# Drone.net
KiCad netlist of a schematic drawn in Altium Designer
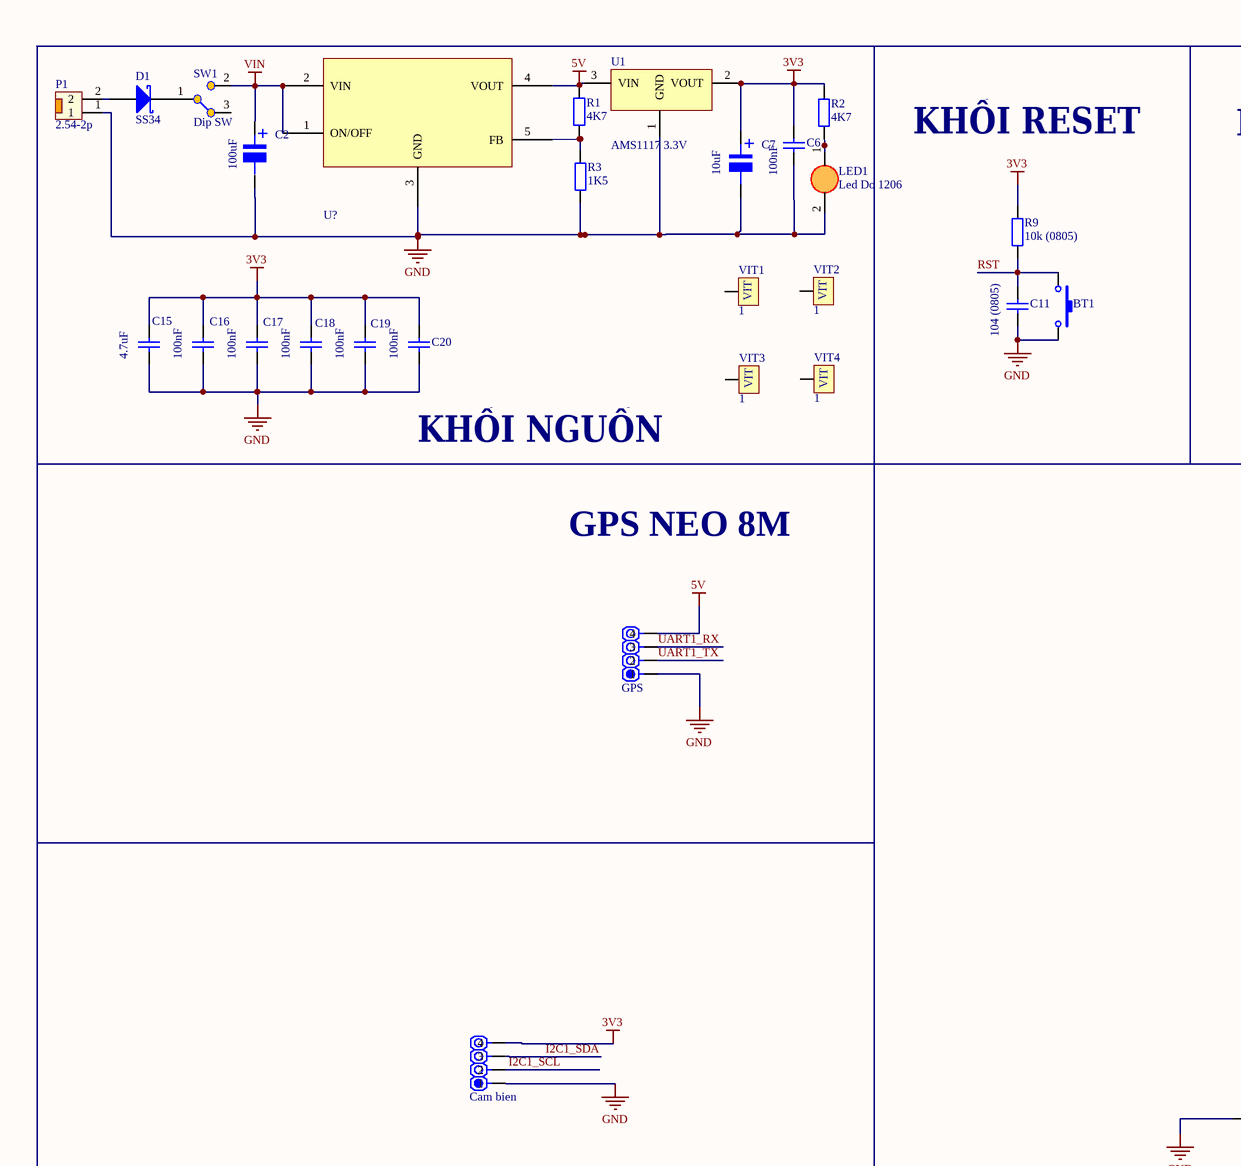
[diagram p0: Drone.SchDoc, top left]
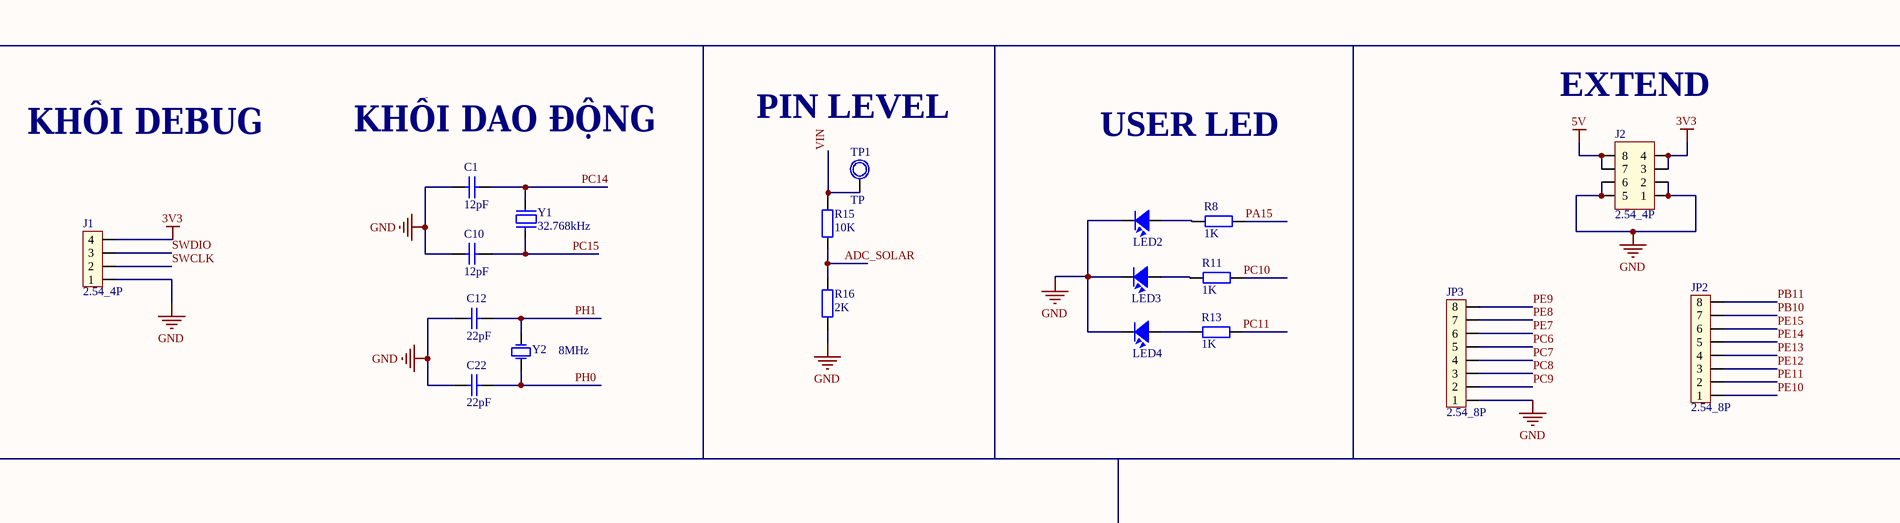
[diagram p1: Drone.SchDoc, top right]
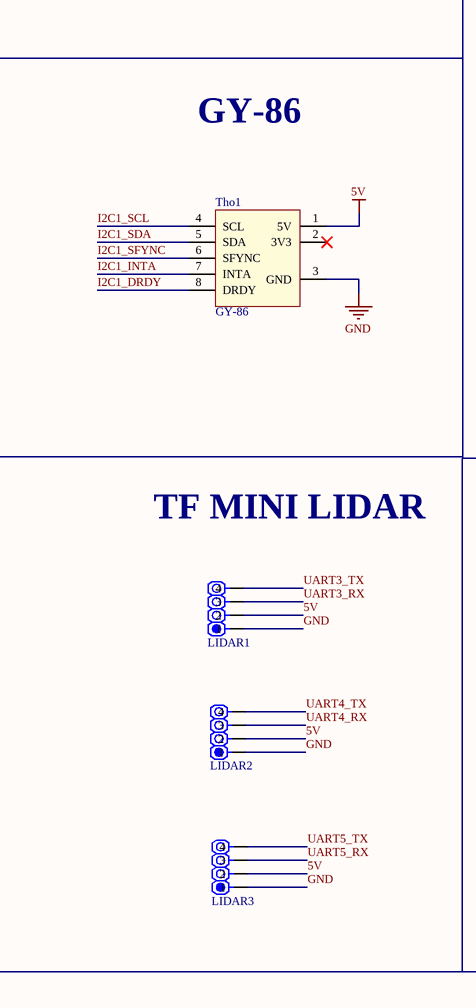
[diagram p2: Drone.SchDoc, bottom left]
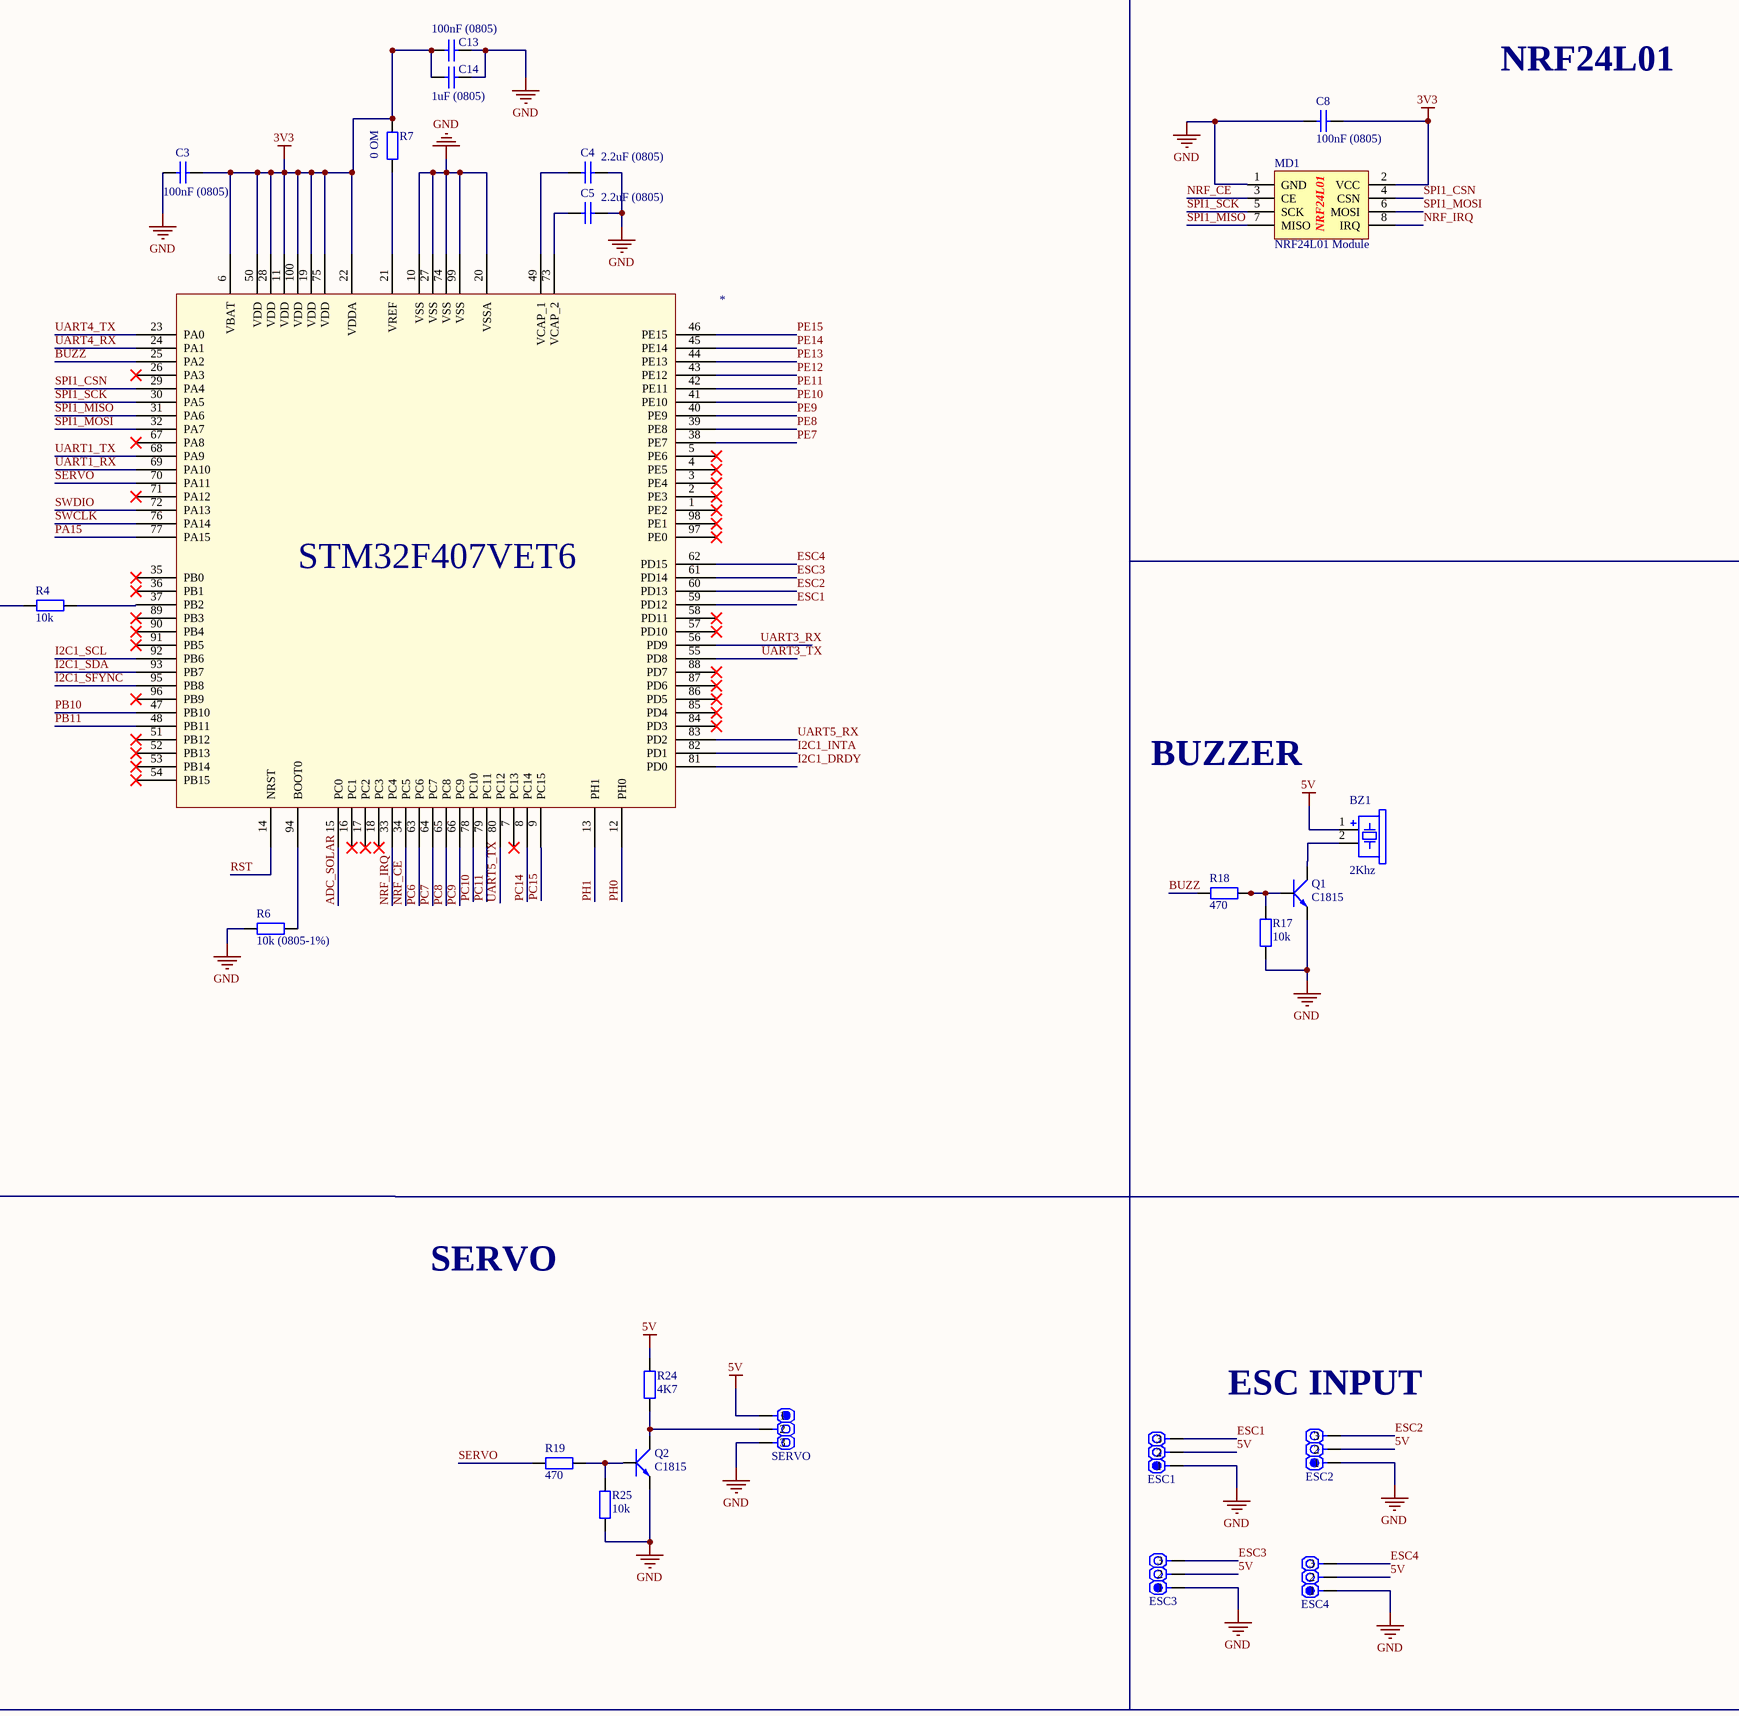
[diagram p3: Drone.SchDoc, bottom right]

(export (version "E")
  (design (tool "Eeschema 10.0.6"))
  (components
    (comp (ref "*")
      (value "STM32F407")
      (footprint "STM32F407Vet6")
      (libsource (lib "STM32f407") (part "STM32F407"))
    )
    (comp (ref "BT1")
      (value "Nút Nhấn 2 Chân 3x6x2.5MM SMD")
      (footprint "Nut Nhan 2 Chan SMD_N")
      (description "Dán")
      (libsource (lib "SCH Chuan") (part "Nut Nhan 2 Chan SMD"))
    )
    (comp (ref "BZ1")
      (value "2Khz")
      (footprint "coi xung")
      (description "Cắm")
      (libsource (lib "SCH Chuan") (part "Coi xung 2Khz"))
    )
    (comp (ref "C1")
      (value "12pF")
      (footprint "tu 0805")
      (description "Dán")
      (libsource (lib "SCH Chuan") (part "Tu 0805 10pF 50V 10%"))
    )
    (comp (ref "C2")
      (value "100uF")
      (footprint "tu nhom 10 (g)")
      (description "Dán")
      (libsource (lib "NhomLib") (part "Tu Nhom 100uF 35V"))
    )
    (comp (ref "C3")
      (value "100nF (0805)")
      (footprint "tu 0805")
      (description "Dán")
      (libsource (lib "SCH Chuan") (part "Tu 0805 220nF 50V 10%"))
    )
    (comp (ref "C4")
      (value "2.2uF (0805)")
      (footprint "tu 0805")
      (description "Dán")
      (libsource (lib "SCH Chuan") (part "Tu 0805 220nF 50V 10%"))
    )
    (comp (ref "C5")
      (value "2.2uF (0805)")
      (footprint "tu 0805")
      (description "Dán")
      (libsource (lib "SCH Chuan") (part "Tu 0805 220nF 50V 10%"))
    )
    (comp (ref "C6")
      (value "100nF")
      (footprint "tu 0805")
      (description "Dán")
      (libsource (lib "NhomLib") (part "Tu 0805 220nF 50V 10%"))
    )
    (comp (ref "C7")
      (value "10uF")
      (footprint "tu nhom 4 (b)")
      (description "Dán")
      (libsource (lib "NhomLib") (part "Tu Nhom 10uF 16V"))
    )
    (comp (ref "C8")
      (value "100nF (0805)")
      (footprint "tu 0805")
      (description "Dán")
      (libsource (lib "SCH Chuan") (part "Tu 0805 220nF 50V 10%"))
    )
    (comp (ref "C10")
      (value "12pF")
      (footprint "tu 0805")
      (description "Dán")
      (libsource (lib "SCH Chuan") (part "Tu 0805 10pF 50V 10%"))
    )
    (comp (ref "C11")
      (value "104 (0805)")
      (footprint "tu 0805")
      (description "Dán")
      (libsource (lib "SCH Chuan") (part "Tu 0805 104 50V 10%"))
    )
    (comp (ref "C12")
      (value "22pF")
      (footprint "tu 0805")
      (description "Dán")
      (libsource (lib "SCH Chuan") (part "Tu 0805 10pF 50V 10%"))
    )
    (comp (ref "C13")
      (value "100nF (0805)")
      (footprint "tu 0805")
      (description "Dán")
      (libsource (lib "SCH Chuan") (part "Tu 0805 220nF 50V 10%"))
    )
    (comp (ref "C14")
      (value "1uF (0805)")
      (footprint "tu 0805")
      (description "Dán")
      (libsource (lib "SCH Chuan") (part "Tu 0805 220nF 50V 10%"))
    )
    (comp (ref "C15")
      (value "4.7uF")
      (footprint "tu 0805")
      (description "Dán")
      (libsource (lib "SCH Chuan") (part "Tu 0805 104 50V 10%"))
    )
    (comp (ref "C16")
      (value "100nF")
      (footprint "tu 0805")
      (description "Dán")
      (libsource (lib "SCH Chuan") (part "Tu 0805 104 50V 10%"))
    )
    (comp (ref "C17")
      (value "100nF")
      (footprint "tu 0805")
      (description "Dán")
      (libsource (lib "SCH Chuan") (part "Tu 0805 104 50V 10%"))
    )
    (comp (ref "C18")
      (value "100nF")
      (footprint "tu 0805")
      (description "Dán")
      (libsource (lib "SCH Chuan") (part "Tu 0805 104 50V 10%"))
    )
    (comp (ref "C19")
      (value "100nF")
      (footprint "tu 0805")
      (description "Dán")
      (libsource (lib "SCH Chuan") (part "Tu 0805 104 50V 10%"))
    )
    (comp (ref "C20")
      (value "100nF")
      (footprint "tu 0805")
      (description "Dán")
      (libsource (lib "SCH Chuan") (part "Tu 0805 104 50V 10%"))
    )
    (comp (ref "C22")
      (value "22pF")
      (footprint "tu 0805")
      (description "Dán")
      (libsource (lib "SCH Chuan") (part "Tu 0805 10pF 50V 10%"))
    )
    (comp (ref "Cam bien")
      (value "IO")
      (footprint "CON.HDR1X4L")
      (description "Header 1x4")
      (fields (field (name "PUBLISHER") "NKIM"))
      (libsource (lib "VPMyLibrary") (part "CON.HDR1x4"))
    )
    (comp (ref "D1")
      (value "SS34")
      (footprint "DIODE_DO214AC_SMA")
      (description "DIODE SCHOTTKY 40V 3A SMA")
      (libsource (lib "NhomLib") (part "SS34"))
    )
    (comp (ref "ESC1")
      (value "IO")
      (footprint "CON.HDR1X3")
      (description "Header 1x3")
      (fields (field (name "PUBLISHER") "NKIM"))
      (libsource (lib "VPMyLibrary") (part "CON.HDR1x3"))
    )
    (comp (ref "ESC2")
      (value "IO")
      (footprint "CON.HDR1X3")
      (description "Header 1x3")
      (fields (field (name "PUBLISHER") "NKIM"))
      (libsource (lib "VPMyLibrary") (part "CON.HDR1x3"))
    )
    (comp (ref "ESC3")
      (value "IO")
      (footprint "CON.HDR1X3")
      (description "Header 1x3")
      (fields (field (name "PUBLISHER") "NKIM"))
      (libsource (lib "VPMyLibrary") (part "CON.HDR1x3"))
    )
    (comp (ref "ESC4")
      (value "IO")
      (footprint "CON.HDR1X3")
      (description "Header 1x3")
      (fields (field (name "PUBLISHER") "NKIM"))
      (libsource (lib "VPMyLibrary") (part "CON.HDR1x3"))
    )
    (comp (ref "GPS")
      (value "IO")
      (footprint "CON.HDR1X4L")
      (description "Header 1x4")
      (fields (field (name "PUBLISHER") "NKIM"))
      (libsource (lib "VPMyLibrary") (part "CON.HDR1x4"))
    )
    (comp (ref "J1")
      (value "2.54_4P")
      (footprint "jump don duc thang 2.54_4p")
      (description "Cắm")
      (libsource (lib "NhomLib") (part "Jump Don Duc Thang 2.54_4P"))
    )
    (comp (ref "J2")
      (value "2.54_4P")
      (footprint "JP4x2")
      (description "Cắm")
      (libsource (lib "NhomLib") (part "Jump Doi Duc 2.54_4Px2"))
    )
    (comp (ref "JP2")
      (value "2.54_8P")
      (footprint "Jump Don Duc Thang 2.54_8p")
      (description "Cắm")
      (libsource (lib "NhomLib") (part "Jump Don Duc 2.54_8P"))
    )
    (comp (ref "JP3")
      (value "2.54_8P")
      (footprint "Jump Don Duc Thang 2.54_8p")
      (description "Cắm")
      (libsource (lib "NhomLib") (part "Jump Don Duc 2.54_8P"))
    )
    (comp (ref "LED1")
      (value "Led Do 1206")
      (footprint "led 1206")
      (description "Dán")
      (libsource (lib "NhomLib") (part "Led 1206 Do"))
    )
    (comp (ref "LED2")
      (value "LED SMD")
      (footprint "SM-LED-0805-Yellow")
      (libsource (lib "syhaunguyen") (part "LED-SMD-0805"))
    )
    (comp (ref "LED3")
      (value "LED SMD")
      (footprint "SM-LED-0805-Green")
      (libsource (lib "syhaunguyen") (part "LED-SMD-0805"))
    )
    (comp (ref "LED4")
      (value "LED SMD")
      (footprint "SM-LED-0805-Blue")
      (libsource (lib "syhaunguyen") (part "LED-SMD-0805"))
    )
    (comp (ref "LIDAR1")
      (value "IO")
      (footprint "CON.HDR1X4L")
      (description "Header 1x4")
      (fields (field (name "PUBLISHER") "NKIM"))
      (libsource (lib "VPMyLibrary") (part "CON.HDR1x4"))
    )
    (comp (ref "LIDAR2")
      (value "IO")
      (footprint "CON.HDR1X4L")
      (description "Header 1x4")
      (fields (field (name "PUBLISHER") "NKIM"))
      (libsource (lib "VPMyLibrary") (part "CON.HDR1x4"))
    )
    (comp (ref "LIDAR3")
      (value "IO")
      (footprint "CON.HDR1X4L")
      (description "Header 1x4")
      (fields (field (name "PUBLISHER") "NKIM"))
      (libsource (lib "VPMyLibrary") (part "CON.HDR1x4"))
    )
    (comp (ref "MD1")
      (value "NRF24L01 Module")
      (footprint "NRF24L01")
      (libsource (lib "Altium_Lib_by_KhueNguyenCreator") (part "NRF24L01 Module"))
    )
    (comp (ref "MIC1")
      (value "U?")
      (footprint "Mic5V")
      (description "3A")
      (libsource (lib "node_mcu") (part "Mic5V"))
    )
    (comp (ref "P1")
      (value "2.54-2p")
      (footprint "Header Duc Thang 2P 2.54")
      (description "Cắm")
      (libsource (lib "NhomLib") (part "Header 2.54-2p Duc Thang"))
    )
    (comp (ref "Q1")
      (value "C1815")
      (footprint "SOT23B")
      (description "NPN 600mW, ECB")
      (libsource (lib "syhaunguyen") (part "C1815"))
    )
    (comp (ref "Q2")
      (value "C1815")
      (footprint "SOT23B")
      (description "NPN 600mW, ECB")
      (libsource (lib "syhaunguyen") (part "C1815"))
    )
    (comp (ref "R1")
      (value "4K7")
      (footprint "tro 0805")
      (description "Dán")
      (libsource (lib "SCH Chuan") (part "Tro 0805 5% 10k"))
    )
    (comp (ref "R2")
      (value "4K7")
      (footprint "tro 0805")
      (description "Dán")
      (libsource (lib "SCH Chuan") (part "Tro 0805 5% 10k"))
    )
    (comp (ref "R3")
      (value "1K5")
      (footprint "tro 0805")
      (description "Dán")
      (libsource (lib "SCH Chuan") (part "Tro 0805 5% 10k"))
    )
    (comp (ref "R4")
      (value "10k")
      (footprint "tro 0805")
      (description "Dán")
      (libsource (lib "SCH Chuan") (part "Tro 0805 1% 10k"))
    )
    (comp (ref "R6")
      (value "10k (0805-1%)")
      (footprint "tro 0805")
      (description "Dán")
      (libsource (lib "SCH Chuan") (part "Tro 0805 1% 10k"))
    )
    (comp (ref "R7")
      (value "0 OM")
      (footprint "tro 0805")
      (description "Dán")
      (libsource (lib "SCH Chuan") (part "Tro 0805 5% 10k"))
    )
    (comp (ref "R8")
      (value "1K")
      (footprint "tro 0805")
      (description "Dán")
      (libsource (lib "SCH Chuan") (part "Tro 0805 5% 470R"))
    )
    (comp (ref "R9")
      (value "10k (0805)")
      (footprint "tro 0805")
      (description "Dán")
      (libsource (lib "SCH Chuan") (part "Tro 0805 5% 10k"))
    )
    (comp (ref "R11")
      (value "1K")
      (footprint "tro 0805")
      (description "Dán")
      (libsource (lib "SCH Chuan") (part "Tro 0805 5% 470R"))
    )
    (comp (ref "R13")
      (value "1K")
      (footprint "tro 0805")
      (description "Dán")
      (libsource (lib "SCH Chuan") (part "Tro 0805 5% 470R"))
    )
    (comp (ref "R15")
      (value "10K")
      (footprint "tro 0805")
      (description "Dán")
      (libsource (lib "SCH Chuan") (part "Tro 0805 5% 10k"))
    )
    (comp (ref "R16")
      (value "2K")
      (footprint "tro 0805")
      (description "Dán")
      (libsource (lib "SCH Chuan") (part "Tro 0805 5% 10k"))
    )
    (comp (ref "R17")
      (value "10k")
      (footprint "tro 0805")
      (description "Dán")
      (libsource (lib "SCH Chuan") (part "Tro 0805 1% 10k"))
    )
    (comp (ref "R18")
      (value "470")
      (footprint "tro 0805")
      (description "Dán")
      (libsource (lib "SCH Chuan") (part "Tro 0805 1% 10k"))
    )
    (comp (ref "R19")
      (value "470")
      (footprint "tro 0805")
      (description "Dán")
      (libsource (lib "SCH Chuan") (part "Tro 0805 1% 10k"))
    )
    (comp (ref "R24")
      (value "4K7")
      (footprint "tro 0805")
      (description "Dán")
      (libsource (lib "SCH Chuan") (part "Tro 0805 1% 10k"))
    )
    (comp (ref "R25")
      (value "10k")
      (footprint "tro 0805")
      (description "Dán")
      (libsource (lib "SCH Chuan") (part "Tro 0805 1% 10k"))
    )
    (comp (ref "SERVO")
      (value "IO")
      (footprint "CON.HDR1X3")
      (description "Header 1x3")
      (fields (field (name "PUBLISHER") "NKIM"))
      (libsource (lib "VPMyLibrary") (part "CON.HDR1x3"))
    )
    (comp (ref "SW1")
      (value "Dip SW")
      (footprint "SW3P")
      (description "Dip Switch 3 pin")
      (libsource (lib "VPMyLibrary") (part "Switch3P"))
    )
    (comp (ref "Tho1") (value "GY-86") (footprint "GY-86") (libsource (lib "JOYSTICK") (part "GY-86")))
    (comp (ref "TP1")
      (value "TP")
      (footprint "TP1")
      (description "Test Point")
      (libsource (lib "syhaunguyen") (part "TP1"))
    )
    (comp (ref "U1")
      (value "AMS1117 3.3V")
      (footprint "SOT223")
      (description "Dán")
      (libsource (lib "NhomLib") (part "AMS1117 3.3V"))
    )
    (comp (ref "VIT1")
      (value "1")
      (footprint "VIT")
      (description "Oc Vit")
      (libsource (lib "NhomLib") (part "VIT"))
    )
    (comp (ref "VIT2")
      (value "1")
      (footprint "VIT")
      (description "Oc Vit")
      (libsource (lib "NhomLib") (part "VIT"))
    )
    (comp (ref "VIT3")
      (value "1")
      (footprint "VIT")
      (description "Oc Vit")
      (libsource (lib "NhomLib") (part "VIT"))
    )
    (comp (ref "VIT4")
      (value "1")
      (footprint "VIT")
      (description "Oc Vit")
      (libsource (lib "NhomLib") (part "VIT"))
    )
    (comp (ref "Y1")
      (value "32.768kHz")
      (footprint "Thach Anh 2 Chan 32,768 KHz")
      (description "Crystal For all Crystal 2pin.")
      (libsource (lib "Altium_Lib_by_KhueNguyenCreator") (part "Thach Anh 2 chan 32,768 Khz"))
    )
    (comp (ref "Y2")
      (value "8MHz")
      (footprint "thach anh 49s smd")
      (description "Dán")
      (libsource (lib "SCH Chuan") (part "Thach anh 8MHz 49S SMD"))
    )
  )
  (nets
    (net (code "1") (name "/ADC_SOLAR") (class "Default")
      (node (ref "*") (pin "15") (pinfunction "PC0_15") (pintype "passive"))
      (node (ref "R15") (pin "1") (pinfunction "1_1") (pintype "passive"))
      (node (ref "R16") (pin "2") (pinfunction "2_2") (pintype "passive"))
    )
    (net (code "2") (name "/BUZZ") (class "Default")
      (node (ref "*") (pin "25") (pinfunction "PA2_25") (pintype "passive"))
      (node (ref "R18") (pin "2") (pinfunction "2_2") (pintype "passive"))
    )
    (net (code "3") (name "/ESC1") (class "Default")
      (node (ref "*") (pin "59") (pinfunction "PD12_59") (pintype "passive"))
      (node (ref "ESC1") (pin "3") (pinfunction "3_3") (pintype "passive"))
    )
    (net (code "4") (name "/ESC2") (class "Default")
      (node (ref "*") (pin "60") (pinfunction "PD13_60") (pintype "passive"))
      (node (ref "ESC2") (pin "3") (pinfunction "3_3") (pintype "passive"))
    )
    (net (code "5") (name "/ESC3") (class "Default")
      (node (ref "*") (pin "61") (pinfunction "PD14_61") (pintype "passive"))
      (node (ref "ESC3") (pin "3") (pinfunction "3_3") (pintype "passive"))
    )
    (net (code "6") (name "/ESC4") (class "Default")
      (node (ref "*") (pin "62") (pinfunction "PD15_62") (pintype "passive"))
      (node (ref "ESC4") (pin "3") (pinfunction "3_3") (pintype "passive"))
    )
    (net (code "7") (name "/I2C1_DRDY") (class "Default")
      (node (ref "*") (pin "81") (pinfunction "PD0_81") (pintype "passive"))
      (node (ref "Tho1") (pin "8") (pinfunction "DRDY_8") (pintype "passive"))
    )
    (net (code "8") (name "/I2C1_INTA") (class "Default")
      (node (ref "*") (pin "82") (pinfunction "PD1_82") (pintype "passive"))
      (node (ref "Tho1") (pin "7") (pinfunction "INTA_7") (pintype "passive"))
    )
    (net (code "9") (name "/I2C1_SCL") (class "Default")
      (node (ref "*") (pin "92") (pinfunction "PB6_92") (pintype "passive"))
      (node (ref "Cam bien") (pin "2") (pinfunction "2_2") (pintype "passive"))
      (node (ref "Tho1") (pin "4") (pinfunction "SCL_4") (pintype "passive"))
    )
    (net (code "10") (name "/I2C1_SDA") (class "Default")
      (node (ref "*") (pin "93") (pinfunction "PB7_93") (pintype "passive"))
      (node (ref "Cam bien") (pin "3") (pinfunction "3_3") (pintype "passive"))
      (node (ref "Tho1") (pin "5") (pinfunction "SDA_5") (pintype "passive"))
    )
    (net (code "11") (name "/I2C1_SFYNC") (class "Default")
      (node (ref "*") (pin "95") (pinfunction "PB8_95") (pintype "passive"))
      (node (ref "Tho1") (pin "6") (pinfunction "SFYNC_6") (pintype "passive"))
    )
    (net (code "12") (name "/NRF_CE") (class "Default")
      (node (ref "*") (pin "34") (pinfunction "PC5_34") (pintype "passive"))
      (node (ref "MD1") (pin "3") (pinfunction "CE_3") (pintype "passive"))
    )
    (net (code "13") (name "/NRF_IRQ") (class "Default")
      (node (ref "*") (pin "33") (pinfunction "PC4_33") (pintype "passive"))
      (node (ref "MD1") (pin "8") (pinfunction "IRQ_8") (pintype "passive"))
    )
    (net (code "14") (name "/PA15") (class "Default")
      (node (ref "*") (pin "77") (pinfunction "PA15_77") (pintype "passive"))
      (node (ref "R8") (pin "2") (pinfunction "2_2") (pintype "passive"))
    )
    (net (code "15") (name "/PB10") (class "Default")
      (node (ref "*") (pin "47") (pinfunction "PB10_47") (pintype "passive"))
      (node (ref "JP2") (pin "7") (pinfunction "7_7") (pintype "passive"))
    )
    (net (code "16") (name "/PB11") (class "Default")
      (node (ref "*") (pin "48") (pinfunction "PB11_48") (pintype "passive"))
      (node (ref "JP2") (pin "8") (pinfunction "8_8") (pintype "passive"))
    )
    (net (code "17") (name "/PC6") (class "Default")
      (node (ref "*") (pin "63") (pinfunction "PC6_63") (pintype "passive"))
      (node (ref "JP3") (pin "5") (pinfunction "5_5") (pintype "passive"))
    )
    (net (code "18") (name "/PC7") (class "Default")
      (node (ref "*") (pin "64") (pinfunction "PC7_64") (pintype "passive"))
      (node (ref "JP3") (pin "4") (pinfunction "4_4") (pintype "passive"))
    )
    (net (code "19") (name "/PC8") (class "Default")
      (node (ref "*") (pin "65") (pinfunction "PC8_65") (pintype "passive"))
      (node (ref "JP3") (pin "3") (pinfunction "3_3") (pintype "passive"))
    )
    (net (code "20") (name "/PC9") (class "Default")
      (node (ref "*") (pin "66") (pinfunction "PC9_66") (pintype "passive"))
      (node (ref "JP3") (pin "2") (pinfunction "2_2") (pintype "passive"))
    )
    (net (code "21") (name "/PC10") (class "Default")
      (node (ref "*") (pin "78") (pinfunction "PC10_78") (pintype "passive"))
      (node (ref "R11") (pin "2") (pinfunction "2_2") (pintype "passive"))
    )
    (net (code "22") (name "/PC11") (class "Default")
      (node (ref "*") (pin "79") (pinfunction "PC11_79") (pintype "passive"))
      (node (ref "R13") (pin "2") (pinfunction "2_2") (pintype "passive"))
    )
    (net (code "23") (name "/PC14") (class "Default")
      (node (ref "*") (pin "8") (pinfunction "PC14_8") (pintype "passive"))
      (node (ref "C1") (pin "1") (pinfunction "1_1") (pintype "passive"))
      (node (ref "Y1") (pin "2") (pinfunction "2_2") (pintype "passive"))
    )
    (net (code "24") (name "/PC15") (class "Default")
      (node (ref "*") (pin "9") (pinfunction "PC15_9") (pintype "passive"))
      (node (ref "C10") (pin "1") (pinfunction "1_1") (pintype "passive"))
      (node (ref "Y1") (pin "1") (pinfunction "1_1") (pintype "passive"))
    )
    (net (code "25") (name "/PE7") (class "Default")
      (node (ref "*") (pin "38") (pinfunction "PE7_38") (pintype "passive"))
      (node (ref "JP3") (pin "6") (pinfunction "6_6") (pintype "passive"))
    )
    (net (code "26") (name "/PE8") (class "Default")
      (node (ref "*") (pin "39") (pinfunction "PE8_39") (pintype "passive"))
      (node (ref "JP3") (pin "7") (pinfunction "7_7") (pintype "passive"))
    )
    (net (code "27") (name "/PE9") (class "Default")
      (node (ref "*") (pin "40") (pinfunction "PE9_40") (pintype "passive"))
      (node (ref "JP3") (pin "8") (pinfunction "8_8") (pintype "passive"))
    )
    (net (code "28") (name "/PE10") (class "Default")
      (node (ref "*") (pin "41") (pinfunction "PE10_41") (pintype "passive"))
      (node (ref "JP2") (pin "1") (pinfunction "1_1") (pintype "passive"))
    )
    (net (code "29") (name "/PE11") (class "Default")
      (node (ref "*") (pin "42") (pinfunction "PE11_42") (pintype "passive"))
      (node (ref "JP2") (pin "2") (pinfunction "2_2") (pintype "passive"))
    )
    (net (code "30") (name "/PE12") (class "Default")
      (node (ref "*") (pin "43") (pinfunction "PE12_43") (pintype "passive"))
      (node (ref "JP2") (pin "3") (pinfunction "3_3") (pintype "passive"))
    )
    (net (code "31") (name "/PE13") (class "Default")
      (node (ref "*") (pin "44") (pinfunction "PE13_44") (pintype "passive"))
      (node (ref "JP2") (pin "4") (pinfunction "4_4") (pintype "passive"))
    )
    (net (code "32") (name "/PE14") (class "Default")
      (node (ref "*") (pin "45") (pinfunction "PE14_45") (pintype "passive"))
      (node (ref "JP2") (pin "5") (pinfunction "5_5") (pintype "passive"))
    )
    (net (code "33") (name "/PE15") (class "Default")
      (node (ref "*") (pin "46") (pinfunction "PE15_46") (pintype "passive"))
      (node (ref "JP2") (pin "6") (pinfunction "6_6") (pintype "passive"))
    )
    (net (code "34") (name "/PH0") (class "Default")
      (node (ref "*") (pin "12") (pinfunction "PH0_12") (pintype "passive"))
      (node (ref "C22") (pin "1") (pinfunction "1_1") (pintype "passive"))
      (node (ref "Y2") (pin "2") (pinfunction "OSC2_2") (pintype "passive"))
    )
    (net (code "35") (name "/PH1") (class "Default")
      (node (ref "*") (pin "13") (pinfunction "PH1_13") (pintype "passive"))
      (node (ref "C12") (pin "1") (pinfunction "1_1") (pintype "passive"))
      (node (ref "Y2") (pin "1") (pinfunction "OSC1_1") (pintype "passive"))
    )
    (net (code "36") (name "/RST") (class "Default")
      (node (ref "*") (pin "14") (pinfunction "NRST_14") (pintype "passive"))
      (node (ref "BT1") (pin "1") (pinfunction "1_1") (pintype "passive"))
      (node (ref "C11") (pin "1") (pinfunction "1_1") (pintype "passive"))
      (node (ref "R9") (pin "1") (pinfunction "1_1") (pintype "passive"))
    )
    (net (code "37") (name "/SERVO") (class "Default")
      (node (ref "*") (pin "70") (pinfunction "PA11_70") (pintype "passive"))
      (node (ref "R19") (pin "2") (pinfunction "2_2") (pintype "passive"))
    )
    (net (code "38") (name "/SPI1_CSN") (class "Default")
      (node (ref "*") (pin "29") (pinfunction "PA4_29") (pintype "passive"))
      (node (ref "MD1") (pin "4") (pinfunction "CSN_4") (pintype "passive"))
    )
    (net (code "39") (name "/SPI1_MISO") (class "Default")
      (node (ref "*") (pin "31") (pinfunction "PA6_31") (pintype "passive"))
      (node (ref "MD1") (pin "7") (pinfunction "MISO_7") (pintype "passive"))
    )
    (net (code "40") (name "/SPI1_MOSI") (class "Default")
      (node (ref "*") (pin "32") (pinfunction "PA7_32") (pintype "passive"))
      (node (ref "MD1") (pin "6") (pinfunction "MOSI_6") (pintype "passive"))
    )
    (net (code "41") (name "/SPI1_SCK") (class "Default")
      (node (ref "*") (pin "30") (pinfunction "PA5_30") (pintype "passive"))
      (node (ref "MD1") (pin "5") (pinfunction "SCK_5") (pintype "passive"))
    )
    (net (code "42") (name "/SWCLK") (class "Default")
      (node (ref "*") (pin "76") (pinfunction "PA14_76") (pintype "passive"))
      (node (ref "J1") (pin "2") (pinfunction "2_2") (pintype "passive"))
    )
    (net (code "43") (name "/SWDIO") (class "Default")
      (node (ref "*") (pin "72") (pinfunction "PA13_72") (pintype "passive"))
      (node (ref "J1") (pin "3") (pinfunction "3_3") (pintype "passive"))
    )
    (net (code "44") (name "/UART1_RX") (class "Default")
      (node (ref "*") (pin "69") (pinfunction "PA10_69") (pintype "passive"))
      (node (ref "GPS") (pin "3") (pinfunction "3_3") (pintype "passive"))
    )
    (net (code "45") (name "/UART1_TX") (class "Default")
      (node (ref "*") (pin "68") (pinfunction "PA9_68") (pintype "passive"))
      (node (ref "GPS") (pin "2") (pinfunction "2_2") (pintype "passive"))
    )
    (net (code "46") (name "/UART3_RX") (class "Default")
      (node (ref "*") (pin "56") (pinfunction "PD9_56") (pintype "passive"))
      (node (ref "LIDAR1") (pin "3") (pinfunction "3_3") (pintype "passive"))
    )
    (net (code "47") (name "/UART3_TX") (class "Default")
      (node (ref "*") (pin "55") (pinfunction "PD8_55") (pintype "passive"))
      (node (ref "LIDAR1") (pin "4") (pinfunction "4_4") (pintype "passive"))
    )
    (net (code "48") (name "/UART4_RX") (class "Default")
      (node (ref "*") (pin "24") (pinfunction "PA1_24") (pintype "passive"))
      (node (ref "LIDAR2") (pin "3") (pinfunction "3_3") (pintype "passive"))
    )
    (net (code "49") (name "/UART4_TX") (class "Default")
      (node (ref "*") (pin "23") (pinfunction "PA0_23") (pintype "passive"))
      (node (ref "LIDAR2") (pin "4") (pinfunction "4_4") (pintype "passive"))
    )
    (net (code "50") (name "/UART5_RX") (class "Default")
      (node (ref "*") (pin "83") (pinfunction "PD2_83") (pintype "passive"))
      (node (ref "LIDAR3") (pin "3") (pinfunction "3_3") (pintype "passive"))
    )
    (net (code "51") (name "/UART5_TX") (class "Default")
      (node (ref "*") (pin "80") (pinfunction "PC12_80") (pintype "passive"))
      (node (ref "LIDAR3") (pin "4") (pinfunction "4_4") (pintype "passive"))
    )
    (net (code "52") (name "3V3") (class "Default")
      (node (ref "*") (pin "100") (pinfunction "VDD_100") (pintype "passive"))
      (node (ref "*") (pin "11") (pinfunction "VDD_11") (pintype "passive"))
      (node (ref "*") (pin "19") (pinfunction "VDD_19") (pintype "passive"))
      (node (ref "*") (pin "22") (pinfunction "VDDA_22") (pintype "passive"))
      (node (ref "*") (pin "28") (pinfunction "VDD_28") (pintype "passive"))
      (node (ref "*") (pin "50") (pinfunction "VDD_50") (pintype "passive"))
      (node (ref "*") (pin "6") (pinfunction "VBAT_6") (pintype "passive"))
      (node (ref "*") (pin "75") (pinfunction "VDD_75") (pintype "passive"))
      (node (ref "C13") (pin "2") (pinfunction "2_2") (pintype "passive"))
      (node (ref "C14") (pin "2") (pinfunction "2_2") (pintype "passive"))
      (node (ref "C15") (pin "1") (pinfunction "1_1") (pintype "passive"))
      (node (ref "C16") (pin "1") (pinfunction "1_1") (pintype "passive"))
      (node (ref "C17") (pin "1") (pinfunction "1_1") (pintype "passive"))
      (node (ref "C18") (pin "1") (pinfunction "1_1") (pintype "passive"))
      (node (ref "C19") (pin "1") (pinfunction "1_1") (pintype "passive"))
      (node (ref "C20") (pin "1") (pinfunction "1_1") (pintype "passive"))
      (node (ref "C3") (pin "1") (pinfunction "1_1") (pintype "passive"))
      (node (ref "C6") (pin "1") (pinfunction "1_1") (pintype "passive"))
      (node (ref "C7") (pin "1") (pinfunction "1_1") (pintype "passive"))
      (node (ref "C8") (pin "2") (pinfunction "2_2") (pintype "passive"))
      (node (ref "Cam bien") (pin "4") (pinfunction "4_4") (pintype "passive"))
      (node (ref "J1") (pin "4") (pinfunction "4_4") (pintype "passive"))
      (node (ref "J2") (pin "3") (pinfunction "3_3") (pintype "passive"))
      (node (ref "J2") (pin "4") (pinfunction "4_4") (pintype "passive"))
      (node (ref "MD1") (pin "2") (pinfunction "VCC_2") (pintype "passive"))
      (node (ref "R2") (pin "1") (pinfunction "1_1") (pintype "passive"))
      (node (ref "R7") (pin "2") (pinfunction "2_2") (pintype "passive"))
      (node (ref "R9") (pin "2") (pinfunction "2_2") (pintype "passive"))
      (node (ref "U1") (pin "2") (pinfunction "VOUT_2") (pintype "passive"))
    )
    (net (code "53") (name "5V") (class "Default")
      (node (ref "BZ1") (pin "1") (pinfunction "1_1") (pintype "passive"))
      (node (ref "ESC1") (pin "2") (pinfunction "2_2") (pintype "passive"))
      (node (ref "ESC2") (pin "2") (pinfunction "2_2") (pintype "passive"))
      (node (ref "ESC3") (pin "2") (pinfunction "2_2") (pintype "passive"))
      (node (ref "ESC4") (pin "2") (pinfunction "2_2") (pintype "passive"))
      (node (ref "GPS") (pin "4") (pinfunction "4_4") (pintype "passive"))
      (node (ref "J2") (pin "7") (pinfunction "7_7") (pintype "passive"))
      (node (ref "J2") (pin "8") (pinfunction "8_8") (pintype "passive"))
      (node (ref "LIDAR1") (pin "2") (pinfunction "2_2") (pintype "passive"))
      (node (ref "LIDAR2") (pin "2") (pinfunction "2_2") (pintype "passive"))
      (node (ref "LIDAR3") (pin "2") (pinfunction "2_2") (pintype "passive"))
      (node (ref "MIC1") (pin "4") (pinfunction "VOUT_4") (pintype "passive"))
      (node (ref "R1") (pin "2") (pinfunction "2_2") (pintype "passive"))
      (node (ref "R24") (pin "2") (pinfunction "2_2") (pintype "passive"))
      (node (ref "SERVO") (pin "1") (pinfunction "1_1") (pintype "passive"))
      (node (ref "Tho1") (pin "1") (pinfunction "5V_1") (pintype "passive"))
      (node (ref "U1") (pin "3") (pinfunction "VIN_3") (pintype "passive"))
    )
    (net (code "54") (name "GND") (class "Default")
      (node (ref "*") (pin "10") (pinfunction "VSS_10") (pintype "passive"))
      (node (ref "*") (pin "20") (pinfunction "VSSA_20") (pintype "passive"))
      (node (ref "*") (pin "27") (pinfunction "VSS_27") (pintype "passive"))
      (node (ref "*") (pin "74") (pinfunction "VSS_74") (pintype "passive"))
      (node (ref "*") (pin "99") (pinfunction "VSS_99") (pintype "passive"))
      (node (ref "BT1") (pin "2") (pinfunction "2_2") (pintype "passive"))
      (node (ref "C1") (pin "2") (pinfunction "2_2") (pintype "passive"))
      (node (ref "C10") (pin "2") (pinfunction "2_2") (pintype "passive"))
      (node (ref "C11") (pin "2") (pinfunction "2_2") (pintype "passive"))
      (node (ref "C12") (pin "2") (pinfunction "2_2") (pintype "passive"))
      (node (ref "C13") (pin "1") (pinfunction "1_1") (pintype "passive"))
      (node (ref "C14") (pin "1") (pinfunction "1_1") (pintype "passive"))
      (node (ref "C15") (pin "2") (pinfunction "2_2") (pintype "passive"))
      (node (ref "C16") (pin "2") (pinfunction "2_2") (pintype "passive"))
      (node (ref "C17") (pin "2") (pinfunction "2_2") (pintype "passive"))
      (node (ref "C18") (pin "2") (pinfunction "2_2") (pintype "passive"))
      (node (ref "C19") (pin "2") (pinfunction "2_2") (pintype "passive"))
      (node (ref "C2") (pin "2") (pinfunction "2_2") (pintype "passive"))
      (node (ref "C20") (pin "2") (pinfunction "2_2") (pintype "passive"))
      (node (ref "C22") (pin "2") (pinfunction "2_2") (pintype "passive"))
      (node (ref "C3") (pin "2") (pinfunction "2_2") (pintype "passive"))
      (node (ref "C4") (pin "1") (pinfunction "1_1") (pintype "passive"))
      (node (ref "C5") (pin "1") (pinfunction "1_1") (pintype "passive"))
      (node (ref "C6") (pin "2") (pinfunction "2_2") (pintype "passive"))
      (node (ref "C7") (pin "2") (pinfunction "2_2") (pintype "passive"))
      (node (ref "C8") (pin "1") (pinfunction "1_1") (pintype "passive"))
      (node (ref "Cam bien") (pin "1") (pinfunction "1_1") (pintype "passive"))
      (node (ref "ESC1") (pin "1") (pinfunction "1_1") (pintype "passive"))
      (node (ref "ESC2") (pin "1") (pinfunction "1_1") (pintype "passive"))
      (node (ref "ESC3") (pin "1") (pinfunction "1_1") (pintype "passive"))
      (node (ref "ESC4") (pin "1") (pinfunction "1_1") (pintype "passive"))
      (node (ref "GPS") (pin "1") (pinfunction "1_1") (pintype "passive"))
      (node (ref "J1") (pin "1") (pinfunction "1_1") (pintype "passive"))
      (node (ref "J2") (pin "1") (pinfunction "1_1") (pintype "passive"))
      (node (ref "J2") (pin "2") (pinfunction "2_2") (pintype "passive"))
      (node (ref "J2") (pin "5") (pinfunction "5_5") (pintype "passive"))
      (node (ref "J2") (pin "6") (pinfunction "6_6") (pintype "passive"))
      (node (ref "JP3") (pin "1") (pinfunction "1_1") (pintype "passive"))
      (node (ref "LED1") (pin "2") (pinfunction "K_2") (pintype "passive"))
      (node (ref "LED2") (pin "2") (pinfunction "2_2") (pintype "passive"))
      (node (ref "LED3") (pin "2") (pinfunction "2_2") (pintype "passive"))
      (node (ref "LED4") (pin "2") (pinfunction "2_2") (pintype "passive"))
      (node (ref "LIDAR1") (pin "1") (pinfunction "1_1") (pintype "passive"))
      (node (ref "LIDAR2") (pin "1") (pinfunction "1_1") (pintype "passive"))
      (node (ref "LIDAR3") (pin "1") (pinfunction "1_1") (pintype "passive"))
      (node (ref "MD1") (pin "1") (pinfunction "GND_1") (pintype "passive"))
      (node (ref "MIC1") (pin "3") (pinfunction "GND_3") (pintype "passive"))
      (node (ref "P1") (pin "1") (pinfunction "1_1") (pintype "passive"))
      (node (ref "Q1") (pin "1") (pinfunction "E_1") (pintype "passive"))
      (node (ref "Q2") (pin "1") (pinfunction "E_1") (pintype "passive"))
      (node (ref "R16") (pin "1") (pinfunction "1_1") (pintype "passive"))
      (node (ref "R17") (pin "1") (pinfunction "1_1") (pintype "passive"))
      (node (ref "R25") (pin "1") (pinfunction "1_1") (pintype "passive"))
      (node (ref "R3") (pin "1") (pinfunction "1_1") (pintype "passive"))
      (node (ref "R4") (pin "1") (pinfunction "1_1") (pintype "passive"))
      (node (ref "R6") (pin "1") (pinfunction "1_1") (pintype "passive"))
      (node (ref "SERVO") (pin "3") (pinfunction "3_3") (pintype "passive"))
      (node (ref "Tho1") (pin "3") (pinfunction "GND_3") (pintype "passive"))
      (node (ref "U1") (pin "1") (pinfunction "GND_1") (pintype "passive"))
    )
    (net (code "55") (name "Net-(*-BOOT0)") (class "Default")
      (node (ref "*") (pin "94") (pinfunction "BOOT0_94") (pintype "passive"))
      (node (ref "R6") (pin "2") (pinfunction "2_2") (pintype "passive"))
    )
    (net (code "56") (name "Net-(*-PB2)") (class "Default")
      (node (ref "*") (pin "37") (pinfunction "PB2_37") (pintype "passive"))
      (node (ref "R4") (pin "2") (pinfunction "2_2") (pintype "passive"))
    )
    (net (code "57") (name "Net-(*-VCAP_1)") (class "Default")
      (node (ref "*") (pin "49") (pinfunction "VCAP_1_49") (pintype "passive"))
      (node (ref "C4") (pin "2") (pinfunction "2_2") (pintype "passive"))
    )
    (net (code "58") (name "Net-(*-VCAP_2)") (class "Default")
      (node (ref "*") (pin "73") (pinfunction "VCAP_2_73") (pintype "passive"))
      (node (ref "C5") (pin "2") (pinfunction "2_2") (pintype "passive"))
    )
    (net (code "59") (name "Net-(*-VREF)") (class "Default")
      (node (ref "*") (pin "21") (pinfunction "VREF_21") (pintype "passive"))
      (node (ref "R7") (pin "1") (pinfunction "1_1") (pintype "passive"))
    )
    (net (code "60") (name "Net-(D1-A)") (class "Default")
      (node (ref "D1") (pin "1") (pinfunction "A_1") (pintype "passive"))
      (node (ref "P1") (pin "2") (pinfunction "2_2") (pintype "passive"))
    )
    (net (code "61") (name "Net-(D1-K)") (class "Default")
      (node (ref "D1") (pin "2") (pinfunction "K_2") (pintype "passive"))
      (node (ref "SW1") (pin "1") (pinfunction "COM_1") (pintype "passive"))
    )
    (net (code "62") (name "Net-(LED1-A)") (class "Default")
      (node (ref "LED1") (pin "1") (pinfunction "A_1") (pintype "passive"))
      (node (ref "R2") (pin "2") (pinfunction "2_2") (pintype "passive"))
    )
    (net (code "63") (name "Net-(LED2-Pad1)") (class "Default")
      (node (ref "LED2") (pin "1") (pinfunction "1_1") (pintype "passive"))
      (node (ref "R8") (pin "1") (pinfunction "1_1") (pintype "passive"))
    )
    (net (code "64") (name "Net-(LED3-Pad1)") (class "Default")
      (node (ref "LED3") (pin "1") (pinfunction "1_1") (pintype "passive"))
      (node (ref "R11") (pin "1") (pinfunction "1_1") (pintype "passive"))
    )
    (net (code "65") (name "Net-(LED4-Pad1)") (class "Default")
      (node (ref "LED4") (pin "1") (pinfunction "1_1") (pintype "passive"))
      (node (ref "R13") (pin "1") (pinfunction "1_1") (pintype "passive"))
    )
    (net (code "66") (name "Net-(MIC1-FB)") (class "Default")
      (node (ref "MIC1") (pin "5") (pinfunction "FB_5") (pintype "passive"))
      (node (ref "R1") (pin "1") (pinfunction "1_1") (pintype "passive"))
      (node (ref "R3") (pin "2") (pinfunction "2_2") (pintype "passive"))
    )
    (net (code "67") (name "Net-(Q1-B)") (class "Default")
      (node (ref "Q1") (pin "3") (pinfunction "B_3") (pintype "passive"))
      (node (ref "R17") (pin "2") (pinfunction "2_2") (pintype "passive"))
      (node (ref "R18") (pin "1") (pinfunction "1_1") (pintype "passive"))
    )
    (net (code "68") (name "Net-(Q1-C)") (class "Default")
      (node (ref "BZ1") (pin "2") (pinfunction "2_2") (pintype "passive"))
      (node (ref "Q1") (pin "2") (pinfunction "C_2") (pintype "passive"))
    )
    (net (code "69") (name "Net-(Q2-B)") (class "Default")
      (node (ref "Q2") (pin "3") (pinfunction "B_3") (pintype "passive"))
      (node (ref "R19") (pin "1") (pinfunction "1_1") (pintype "passive"))
      (node (ref "R25") (pin "2") (pinfunction "2_2") (pintype "passive"))
    )
    (net (code "70") (name "Net-(Q2-C)") (class "Default")
      (node (ref "Q2") (pin "2") (pinfunction "C_2") (pintype "passive"))
      (node (ref "R24") (pin "1") (pinfunction "1_1") (pintype "passive"))
      (node (ref "SERVO") (pin "2") (pinfunction "2_2") (pintype "passive"))
    )
    (net (code "71") (name "VIN") (class "Default")
      (node (ref "C2") (pin "1") (pinfunction "1_1") (pintype "passive"))
      (node (ref "MIC1") (pin "1") (pinfunction "ON/OFF_1") (pintype "passive"))
      (node (ref "MIC1") (pin "2") (pinfunction "VIN_2") (pintype "passive"))
      (node (ref "R15") (pin "2") (pinfunction "2_2") (pintype "passive"))
      (node (ref "SW1") (pin "2") (pinfunction "NC_2") (pintype "passive"))
      (node (ref "TP1") (pin "1") (pinfunction "1_1") (pintype "passive"))
    )
    (net (code "72") (name "unconnected-(*-PA3-Pad26)") (class "Default")
      (node (ref "*") (pin "26") (pinfunction "PA3_26") (pintype "passive+no_connect"))
    )
    (net (code "73") (name "unconnected-(*-PA8-Pad67)") (class "Default")
      (node (ref "*") (pin "67") (pinfunction "PA8_67") (pintype "passive+no_connect"))
    )
    (net (code "74") (name "unconnected-(*-PA12-Pad71)") (class "Default")
      (node (ref "*") (pin "71") (pinfunction "PA12_71") (pintype "passive+no_connect"))
    )
    (net (code "75") (name "unconnected-(*-PB0-Pad35)") (class "Default")
      (node (ref "*") (pin "35") (pinfunction "PB0_35") (pintype "passive+no_connect"))
    )
    (net (code "76") (name "unconnected-(*-PB1-Pad36)") (class "Default")
      (node (ref "*") (pin "36") (pinfunction "PB1_36") (pintype "passive+no_connect"))
    )
    (net (code "77") (name "unconnected-(*-PB3-Pad89)") (class "Default")
      (node (ref "*") (pin "89") (pinfunction "PB3_89") (pintype "passive+no_connect"))
    )
    (net (code "78") (name "unconnected-(*-PB4-Pad90)") (class "Default")
      (node (ref "*") (pin "90") (pinfunction "PB4_90") (pintype "passive+no_connect"))
    )
    (net (code "79") (name "unconnected-(*-PB5-Pad91)") (class "Default")
      (node (ref "*") (pin "91") (pinfunction "PB5_91") (pintype "passive+no_connect"))
    )
    (net (code "80") (name "unconnected-(*-PB9-Pad96)") (class "Default")
      (node (ref "*") (pin "96") (pinfunction "PB9_96") (pintype "passive+no_connect"))
    )
    (net (code "81") (name "unconnected-(*-PB12-Pad51)") (class "Default")
      (node (ref "*") (pin "51") (pinfunction "PB12_51") (pintype "passive+no_connect"))
    )
    (net (code "82") (name "unconnected-(*-PB13-Pad52)") (class "Default")
      (node (ref "*") (pin "52") (pinfunction "PB13_52") (pintype "passive+no_connect"))
    )
    (net (code "83") (name "unconnected-(*-PB14-Pad53)") (class "Default")
      (node (ref "*") (pin "53") (pinfunction "PB14_53") (pintype "passive+no_connect"))
    )
    (net (code "84") (name "unconnected-(*-PB15-Pad54)") (class "Default")
      (node (ref "*") (pin "54") (pinfunction "PB15_54") (pintype "passive+no_connect"))
    )
    (net (code "85") (name "unconnected-(*-PC1-Pad16)") (class "Default")
      (node (ref "*") (pin "16") (pinfunction "PC1_16") (pintype "passive+no_connect"))
    )
    (net (code "86") (name "unconnected-(*-PC2-Pad17)") (class "Default")
      (node (ref "*") (pin "17") (pinfunction "PC2_17") (pintype "passive+no_connect"))
    )
    (net (code "87") (name "unconnected-(*-PC3-Pad18)") (class "Default")
      (node (ref "*") (pin "18") (pinfunction "PC3_18") (pintype "passive+no_connect"))
    )
    (net (code "88") (name "unconnected-(*-PC13-Pad7)") (class "Default")
      (node (ref "*") (pin "7") (pinfunction "PC13_7") (pintype "passive+no_connect"))
    )
    (net (code "89") (name "unconnected-(*-PD3-Pad84)") (class "Default")
      (node (ref "*") (pin "84") (pinfunction "PD3_84") (pintype "passive+no_connect"))
    )
    (net (code "90") (name "unconnected-(*-PD4-Pad85)") (class "Default")
      (node (ref "*") (pin "85") (pinfunction "PD4_85") (pintype "passive+no_connect"))
    )
    (net (code "91") (name "unconnected-(*-PD5-Pad86)") (class "Default")
      (node (ref "*") (pin "86") (pinfunction "PD5_86") (pintype "passive+no_connect"))
    )
    (net (code "92") (name "unconnected-(*-PD6-Pad87)") (class "Default")
      (node (ref "*") (pin "87") (pinfunction "PD6_87") (pintype "passive+no_connect"))
    )
    (net (code "93") (name "unconnected-(*-PD7-Pad88)") (class "Default")
      (node (ref "*") (pin "88") (pinfunction "PD7_88") (pintype "passive+no_connect"))
    )
    (net (code "94") (name "unconnected-(*-PD10-Pad57)") (class "Default")
      (node (ref "*") (pin "57") (pinfunction "PD10_57") (pintype "passive+no_connect"))
    )
    (net (code "95") (name "unconnected-(*-PD11-Pad58)") (class "Default")
      (node (ref "*") (pin "58") (pinfunction "PD11_58") (pintype "passive+no_connect"))
    )
    (net (code "96") (name "unconnected-(*-PE0-Pad97)") (class "Default")
      (node (ref "*") (pin "97") (pinfunction "PE0_97") (pintype "passive+no_connect"))
    )
    (net (code "97") (name "unconnected-(*-PE1-Pad98)") (class "Default")
      (node (ref "*") (pin "98") (pinfunction "PE1_98") (pintype "passive+no_connect"))
    )
    (net (code "98") (name "unconnected-(*-PE2-Pad1)") (class "Default")
      (node (ref "*") (pin "1") (pinfunction "PE2_1") (pintype "passive+no_connect"))
    )
    (net (code "99") (name "unconnected-(*-PE3-Pad2)") (class "Default")
      (node (ref "*") (pin "2") (pinfunction "PE3_2") (pintype "passive+no_connect"))
    )
    (net (code "100") (name "unconnected-(*-PE4-Pad3)") (class "Default")
      (node (ref "*") (pin "3") (pinfunction "PE4_3") (pintype "passive+no_connect"))
    )
    (net (code "101") (name "unconnected-(*-PE5-Pad4)") (class "Default")
      (node (ref "*") (pin "4") (pinfunction "PE5_4") (pintype "passive+no_connect"))
    )
    (net (code "102") (name "unconnected-(*-PE6-Pad5)") (class "Default")
      (node (ref "*") (pin "5") (pinfunction "PE6_5") (pintype "passive+no_connect"))
    )
    (net (code "103") (name "unconnected-(SW1-NO-Pad3)") (class "Default")
      (node (ref "SW1") (pin "3") (pinfunction "NO_3") (pintype "passive"))
    )
    (net (code "104") (name "unconnected-(Tho1-3V3-Pad2)") (class "Default")
      (node (ref "Tho1") (pin "2") (pinfunction "3V3_2") (pintype "passive+no_connect"))
    )
    (net (code "105") (name "unconnected-(VIT1-1-PadVIT1)") (class "Default")
      (node (ref "VIT1") (pin "VIT1") (pinfunction "1_VIT1") (pintype "passive"))
    )
    (net (code "106") (name "unconnected-(VIT2-1-PadVIT1)") (class "Default")
      (node (ref "VIT2") (pin "VIT1") (pinfunction "1_VIT1") (pintype "passive"))
    )
    (net (code "107") (name "unconnected-(VIT3-1-PadVIT1)") (class "Default")
      (node (ref "VIT3") (pin "VIT1") (pinfunction "1_VIT1") (pintype "passive"))
    )
    (net (code "108") (name "unconnected-(VIT4-1-PadVIT1)") (class "Default")
      (node (ref "VIT4") (pin "VIT1") (pinfunction "1_VIT1") (pintype "passive"))
    )
  )
)
